# Schematic_Processo_Seletivo.net
KiCad netlist of a schematic drawn in Altium Designer
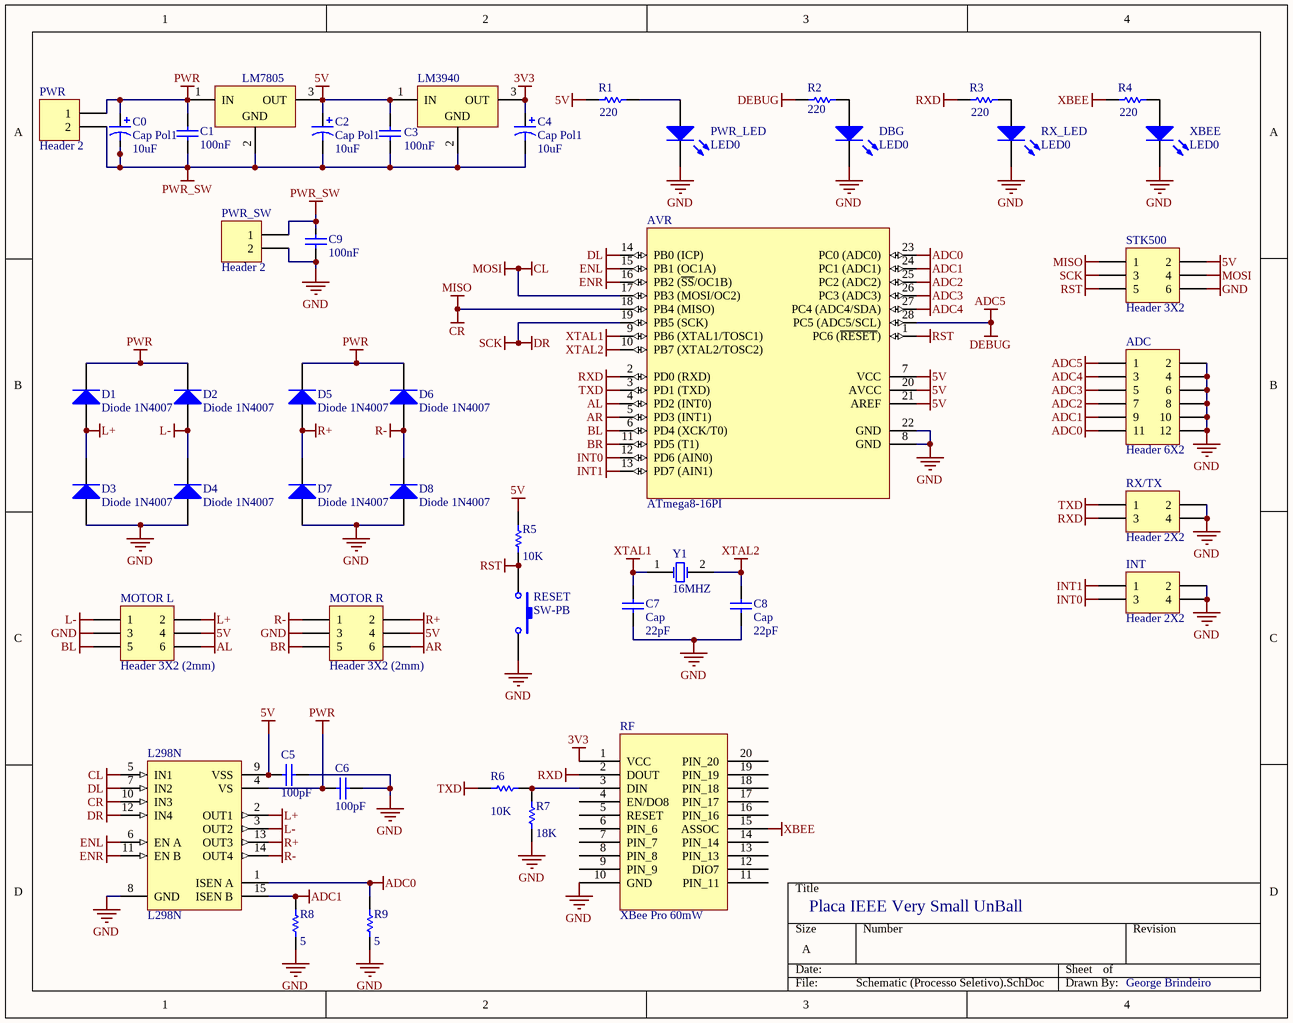
[diagram p0: Schematic (Processo Seletivo).SchDoc]

(export (version "E")
  (design (tool "Eeschema 10.0.6"))
  (components
    (comp (ref "ADC")
      (value "Header 6X2")
      (footprint "HDR2X6")
      (description "Header, 6-Pin, Dual row")
      (fields (field (name "PUBLISHER") "Altium Limited"))
      (libsource (lib "Miscellaneous Connectors") (part "Header 6X2"))
    )
    (comp (ref "AVR")
      (value "ATmega8-16PI")
      (footprint "28P3")
      (description "8-Bit AVR Microcontroller with 8K Bytes of In-System Programmable Flash Memory")
      (fields (field (name "PUBLISHER") "Altium Limited"))
      (libsource (lib "Atmel Microcontroller 8-Bit AVR") (part "ATmega8-16PI"))
    )
    (comp (ref "C0")
      (value "Cap Pol1")
      (footprint "B")
      (description "Polarized Capacitor (Radial)")
      (fields (field (name "ALTIUM_VALUE") "10uF") (field (name "PUBLISHER") "Altium Limited"))
      (libsource (lib "Miscellaneous Devices") (part "Cap Pol1"))
    )
    (comp (ref "C1")
      (value "100nF")
      (footprint "C_NANO_HOLES")
      (description "Capacitor")
      (fields (field (name "Comment") "Cap") (field (name "PUBLISHER") "Altium Limited"))
      (libsource (lib "Miscellaneous Devices") (part "Cap"))
    )
    (comp (ref "C2")
      (value "Cap Pol1")
      (footprint "B")
      (description "Polarized Capacitor (Radial)")
      (fields (field (name "ALTIUM_VALUE") "10uF") (field (name "PUBLISHER") "Altium Limited"))
      (libsource (lib "Miscellaneous Devices") (part "Cap Pol1"))
    )
    (comp (ref "C3")
      (value "100nF")
      (footprint "C_NANO_HOLES")
      (description "Capacitor")
      (fields (field (name "Comment") "Cap") (field (name "PUBLISHER") "Altium Limited"))
      (libsource (lib "Miscellaneous Devices") (part "Cap"))
    )
    (comp (ref "C4")
      (value "Cap Pol1")
      (footprint "B")
      (description "Polarized Capacitor (Radial)")
      (fields (field (name "ALTIUM_VALUE") "10uF") (field (name "PUBLISHER") "Altium Limited"))
      (libsource (lib "Miscellaneous Devices") (part "Cap Pol1"))
    )
    (comp (ref "C5")
      (value "100pF")
      (footprint "C_NANO_HOLES")
      (description "Capacitor")
      (fields (field (name "Comment") "Cap") (field (name "PUBLISHER") "Altium Limited"))
      (libsource (lib "Miscellaneous Devices") (part "Cap"))
    )
    (comp (ref "C6")
      (value "100pF")
      (footprint "C_NANO_HOLES")
      (description "Capacitor")
      (fields (field (name "Comment") "Cap") (field (name "PUBLISHER") "Altium Limited"))
      (libsource (lib "Miscellaneous Devices") (part "Cap"))
    )
    (comp (ref "C7")
      (value "Cap")
      (footprint "C_NANO_HOLES")
      (description "Capacitor")
      (fields (field (name "ALTIUM_VALUE") "22pF") (field (name "PUBLISHER") "Altium Limited"))
      (libsource (lib "Miscellaneous Devices") (part "Cap"))
    )
    (comp (ref "C8")
      (value "Cap")
      (footprint "C_NANO_HOLES")
      (description "Capacitor")
      (fields (field (name "ALTIUM_VALUE") "22pF") (field (name "PUBLISHER") "Altium Limited"))
      (libsource (lib "Miscellaneous Devices") (part "Cap"))
    )
    (comp (ref "C9")
      (value "100nF")
      (footprint "C_NANO_HOLES")
      (description "Capacitor")
      (fields (field (name "Comment") "Cap") (field (name "PUBLISHER") "Altium Limited"))
      (libsource (lib "Miscellaneous Devices") (part "Cap"))
    )
    (comp (ref "D1")
      (value "Diode 1N4007")
      (footprint "DO-41")
      (description "1 Amp General Purpose Rectifier")
      (fields (field (name "PUBLISHER") "Altium Limited"))
      (libsource (lib "Miscellaneous Devices") (part "Diode 1N4007"))
    )
    (comp (ref "D2")
      (value "Diode 1N4007")
      (footprint "DO-41")
      (description "1 Amp General Purpose Rectifier")
      (fields (field (name "PUBLISHER") "Altium Limited"))
      (libsource (lib "Miscellaneous Devices") (part "Diode 1N4007"))
    )
    (comp (ref "D3")
      (value "Diode 1N4007")
      (footprint "DO-41")
      (description "1 Amp General Purpose Rectifier")
      (fields (field (name "PUBLISHER") "Altium Limited"))
      (libsource (lib "Miscellaneous Devices") (part "Diode 1N4007"))
    )
    (comp (ref "D4")
      (value "Diode 1N4007")
      (footprint "DO-41")
      (description "1 Amp General Purpose Rectifier")
      (fields (field (name "PUBLISHER") "Altium Limited"))
      (libsource (lib "Miscellaneous Devices") (part "Diode 1N4007"))
    )
    (comp (ref "D5")
      (value "Diode 1N4007")
      (footprint "DO-41")
      (description "1 Amp General Purpose Rectifier")
      (fields (field (name "PUBLISHER") "Altium Limited"))
      (libsource (lib "Miscellaneous Devices") (part "Diode 1N4007"))
    )
    (comp (ref "D6")
      (value "Diode 1N4007")
      (footprint "DO-41")
      (description "1 Amp General Purpose Rectifier")
      (fields (field (name "PUBLISHER") "Altium Limited"))
      (libsource (lib "Miscellaneous Devices") (part "Diode 1N4007"))
    )
    (comp (ref "D7")
      (value "Diode 1N4007")
      (footprint "DO-41")
      (description "1 Amp General Purpose Rectifier")
      (fields (field (name "PUBLISHER") "Altium Limited"))
      (libsource (lib "Miscellaneous Devices") (part "Diode 1N4007"))
    )
    (comp (ref "D8")
      (value "Diode 1N4007")
      (footprint "DO-41")
      (description "1 Amp General Purpose Rectifier")
      (fields (field (name "PUBLISHER") "Altium Limited"))
      (libsource (lib "Miscellaneous Devices") (part "Diode 1N4007"))
    )
    (comp (ref "DBG")
      (value "LED0")
      (footprint "B")
      (description "Typical INFRARED GaAs LED")
      (fields (field (name "PUBLISHER") "Altium Limited"))
      (libsource (lib "Miscellaneous Devices") (part "LED0"))
    )
    (comp (ref "INT")
      (value "Header 2X2")
      (footprint "HDR2X2")
      (description "Header, 2-Pin, Dual row")
      (fields (field (name "PUBLISHER") "Altium Limited"))
      (libsource (lib "Miscellaneous Connectors") (part "Header 2X2"))
    )
    (comp (ref "L298N")
      (value "L298N")
      (footprint "Multiwatt15V")
      (description "Dual Full Bridge Driver")
      (fields (field (name "PUBLISHER") "Altium Limited"))
      (libsource (lib "ST Interface DC Motor Controller") (part "L298N"))
    )
    (comp (ref "LM3940")
      (value "LM3940IT-3.3")
      (footprint "T03B")
      (description "1A Low Dropout Regulator for 5V to 3.3V Conversion")
      (fields
        (field (name "MANUFACTURER") "National Semiconductor")
        (field (name "DIGIKEYPARTNUMBER") "LM3940IT-3.3-ND")
        (field (name "PUBLISHER") "Altium Limited")
      )
      (libsource (lib "NSC LDO") (part "LM3940IT-3.3"))
    )
    (comp (ref "LM7805")
      (value "µA7805CKC")
      (footprint "KC03")
      (description "Positive-Voltage Regulator")
      (fields (field (name "PUBLISHER") "Altium Limited"))
      (libsource (lib "TI Power Mgt Voltage Regulator") (part "µA7805CKC"))
    )
    (comp (ref "MOTOR L")
      (value "Header 3X2 (2mm)")
      (footprint "HDR2x3_2MM")
      (description "Header, 3-Pin, Dual row")
      (fields (field (name "PUBLISHER") "Altium Limited"))
      (libsource (lib "Miscellaneous Connectors") (part "Header 3X2"))
    )
    (comp (ref "MOTOR R")
      (value "Header 3X2 (2mm)")
      (footprint "HDR2x3_2MM")
      (description "Header, 3-Pin, Dual row")
      (fields (field (name "PUBLISHER") "Altium Limited"))
      (libsource (lib "Miscellaneous Connectors") (part "Header 3X2"))
    )
    (comp (ref "PWR")
      (value "Header 2")
      (footprint "HDR1X2")
      (description "Header, 2-Pin")
      (fields (field (name "PUBLISHER") "Altium Limited"))
      (libsource (lib "Miscellaneous Connectors") (part "Header 2"))
    )
    (comp (ref "PWR_LED")
      (value "LED0")
      (footprint "B")
      (description "Typical INFRARED GaAs LED")
      (fields (field (name "PUBLISHER") "Altium Limited"))
      (libsource (lib "Miscellaneous Devices") (part "LED0"))
    )
    (comp (ref "PWR_SW")
      (value "Header 2")
      (footprint "HDR1X2")
      (description "Header, 2-Pin")
      (fields (field (name "PUBLISHER") "Altium Limited"))
      (libsource (lib "Miscellaneous Connectors") (part "Header 2"))
    )
    (comp (ref "R1")
      (value "220")
      (footprint "AXIAL-0.3")
      (description "Resistor")
      (fields (field (name "PUBLISHER") "Altium Limited"))
      (libsource (lib "Miscellaneous Devices") (part "Res1"))
    )
    (comp (ref "R2")
      (value "220")
      (footprint "AXIAL-0.3")
      (description "Resistor")
      (fields (field (name "PUBLISHER") "Altium Limited"))
      (libsource (lib "Miscellaneous Devices") (part "Res1"))
    )
    (comp (ref "R3")
      (value "220")
      (footprint "AXIAL-0.3")
      (description "Resistor")
      (fields (field (name "PUBLISHER") "Altium Limited"))
      (libsource (lib "Miscellaneous Devices") (part "Res1"))
    )
    (comp (ref "R4")
      (value "220")
      (footprint "AXIAL-0.3")
      (description "Resistor")
      (fields (field (name "PUBLISHER") "Altium Limited"))
      (libsource (lib "Miscellaneous Devices") (part "Res1"))
    )
    (comp (ref "R5")
      (value "10K")
      (footprint "AXIAL-0.3")
      (description "Resistor")
      (fields (field (name "PUBLISHER") "Altium Limited"))
      (libsource (lib "Miscellaneous Devices") (part "Res1"))
    )
    (comp (ref "R6")
      (value "10K")
      (footprint "AXIAL-0.3")
      (description "Resistor")
      (fields (field (name "PUBLISHER") "Altium Limited"))
      (libsource (lib "Miscellaneous Devices") (part "Res1"))
    )
    (comp (ref "R7")
      (value "18K")
      (footprint "AXIAL-0.3")
      (description "Resistor")
      (fields (field (name "PUBLISHER") "Altium Limited"))
      (libsource (lib "Miscellaneous Devices") (part "Res1"))
    )
    (comp (ref "R8")
      (value "5")
      (footprint "AXIAL-0.3")
      (description "Resistor")
      (fields (field (name "PUBLISHER") "Altium Limited"))
      (libsource (lib "Miscellaneous Devices") (part "Res1"))
    )
    (comp (ref "R9")
      (value "5")
      (footprint "AXIAL-0.3")
      (description "Resistor")
      (fields (field (name "PUBLISHER") "Altium Limited"))
      (libsource (lib "Miscellaneous Devices") (part "Res1"))
    )
    (comp (ref "RESET")
      (value "SW-PB")
      (footprint "PUSHBUTTON")
      (description "Switch")
      (fields (field (name "PUBLISHER") "Altium Limited"))
      (libsource (lib "Miscellaneous Devices") (part "SW-PB"))
    )
    (comp (ref "RF") (value "XBee Pro 60mW") (footprint "XBEE_PRO") (libsource (lib "Schlib") (part "XBee")))
    (comp (ref "RX/TX")
      (value "Header 2X2")
      (footprint "HDR2X2")
      (description "Header, 2-Pin, Dual row")
      (fields (field (name "PUBLISHER") "Altium Limited"))
      (libsource (lib "Miscellaneous Connectors") (part "Header 2X2"))
    )
    (comp (ref "RX_LED")
      (value "LED0")
      (footprint "B")
      (description "Typical INFRARED GaAs LED")
      (fields (field (name "PUBLISHER") "Altium Limited"))
      (libsource (lib "Miscellaneous Devices") (part "LED0"))
    )
    (comp (ref "STK500")
      (value "Header 3X2")
      (footprint "HDR2X3")
      (description "Header, 3-Pin, Dual row")
      (fields (field (name "PUBLISHER") "Altium Limited"))
      (libsource (lib "Miscellaneous Connectors") (part "Header 3X2"))
    )
    (comp (ref "XBEE")
      (value "LED0")
      (footprint "B")
      (description "Typical INFRARED GaAs LED")
      (fields (field (name "PUBLISHER") "Altium Limited"))
      (libsource (lib "Miscellaneous Devices") (part "LED0"))
    )
    (comp (ref "Y1")
      (value "16MHZ")
      (footprint "BCY-W2/E4.7")
      (description "Crystal Oscillator")
      (fields (field (name "PUBLISHER") "Altium Limited"))
      (libsource (lib "ECS Crystal Oscillator") (part "ECS-120-32-1"))
    )
  )
  (nets
    (net (code "1") (name "3V3") (class "Default")
      (node (ref "C4") (pin "1") (pinfunction "1_1") (pintype "passive"))
      (node (ref "LM3940") (pin "3") (pinfunction "OUT_3") (pintype "power_in"))
      (node (ref "RF") (pin "1") (pinfunction "VCC_1") (pintype "passive"))
    )
    (net (code "2") (name "5V") (class "Default")
      (node (ref "AVR") (pin "20") (pinfunction "AVCC_20") (pintype "power_in"))
      (node (ref "AVR") (pin "21") (pinfunction "AREF_21") (pintype "passive"))
      (node (ref "AVR") (pin "7") (pinfunction "VCC_7") (pintype "power_in"))
      (node (ref "C2") (pin "1") (pinfunction "1_1") (pintype "passive"))
      (node (ref "C3") (pin "1") (pinfunction "1_1") (pintype "passive"))
      (node (ref "C5") (pin "1") (pinfunction "1_1") (pintype "passive"))
      (node (ref "L298N") (pin "9") (pinfunction "VSS_9") (pintype "power_in"))
      (node (ref "LM3940") (pin "1") (pinfunction "IN_1") (pintype "power_in"))
      (node (ref "LM7805") (pin "3") (pinfunction "OUT_3") (pintype "power_in"))
      (node (ref "MOTOR L") (pin "4") (pinfunction "4_4") (pintype "passive"))
      (node (ref "MOTOR R") (pin "4") (pinfunction "4_4") (pintype "passive"))
      (node (ref "R1") (pin "1") (pinfunction "1_1") (pintype "passive"))
      (node (ref "R5") (pin "2") (pinfunction "2_2") (pintype "passive"))
      (node (ref "STK500") (pin "2") (pinfunction "2_2") (pintype "passive"))
    )
    (net (code "3") (name "ADC0") (class "Default")
      (node (ref "ADC") (pin "11") (pinfunction "11_11") (pintype "passive"))
      (node (ref "AVR") (pin "23") (pinfunction "PC0_(ADC0)_23") (pintype "bidirectional"))
      (node (ref "L298N") (pin "1") (pinfunction "ISEN_A_1") (pintype "passive"))
      (node (ref "R9") (pin "2") (pinfunction "2_2") (pintype "passive"))
    )
    (net (code "4") (name "ADC1") (class "Default")
      (node (ref "ADC") (pin "9") (pinfunction "9_9") (pintype "passive"))
      (node (ref "AVR") (pin "24") (pinfunction "PC1_(ADC1)_24") (pintype "bidirectional"))
      (node (ref "L298N") (pin "15") (pinfunction "ISEN_B_15") (pintype "passive"))
      (node (ref "R8") (pin "2") (pinfunction "2_2") (pintype "passive"))
    )
    (net (code "5") (name "ADC2") (class "Default")
      (node (ref "ADC") (pin "7") (pinfunction "7_7") (pintype "passive"))
      (node (ref "AVR") (pin "25") (pinfunction "PC2_(ADC2)_25") (pintype "bidirectional"))
    )
    (net (code "6") (name "ADC3") (class "Default")
      (node (ref "ADC") (pin "5") (pinfunction "5_5") (pintype "passive"))
      (node (ref "AVR") (pin "26") (pinfunction "PC3_(ADC3)_26") (pintype "bidirectional"))
    )
    (net (code "7") (name "ADC4") (class "Default")
      (node (ref "ADC") (pin "3") (pinfunction "3_3") (pintype "passive"))
      (node (ref "AVR") (pin "27") (pinfunction "PC4_(ADC4/SDA)_27") (pintype "bidirectional"))
    )
    (net (code "8") (name "ADC5") (class "Default")
      (node (ref "ADC") (pin "1") (pinfunction "1_1") (pintype "passive"))
      (node (ref "AVR") (pin "28") (pinfunction "PC5_(ADC5/SCL)_28") (pintype "bidirectional"))
      (node (ref "R2") (pin "1") (pinfunction "1_1") (pintype "passive"))
    )
    (net (code "9") (name "AL") (class "Default")
      (node (ref "AVR") (pin "4") (pinfunction "PD2_(INT0)_4") (pintype "bidirectional"))
      (node (ref "MOTOR L") (pin "6") (pinfunction "6_6") (pintype "passive"))
    )
    (net (code "10") (name "AR") (class "Default")
      (node (ref "AVR") (pin "5") (pinfunction "PD3_(INT1)_5") (pintype "bidirectional"))
      (node (ref "MOTOR R") (pin "6") (pinfunction "6_6") (pintype "passive"))
    )
    (net (code "11") (name "BL") (class "Default")
      (node (ref "AVR") (pin "6") (pinfunction "PD4_(XCK/T0)_6") (pintype "bidirectional"))
      (node (ref "MOTOR L") (pin "5") (pinfunction "5_5") (pintype "passive"))
    )
    (net (code "12") (name "BR") (class "Default")
      (node (ref "AVR") (pin "11") (pinfunction "PD5_(T1)_11") (pintype "bidirectional"))
      (node (ref "MOTOR R") (pin "5") (pinfunction "5_5") (pintype "passive"))
    )
    (net (code "13") (name "CL") (class "Default")
      (node (ref "AVR") (pin "17") (pinfunction "PB3_(MOSI/OC2)_17") (pintype "bidirectional"))
      (node (ref "L298N") (pin "5") (pinfunction "IN1_5") (pintype "input"))
      (node (ref "STK500") (pin "4") (pinfunction "4_4") (pintype "passive"))
    )
    (net (code "14") (name "CR") (class "Default")
      (node (ref "AVR") (pin "18") (pinfunction "PB4_(MISO)_18") (pintype "bidirectional"))
      (node (ref "L298N") (pin "10") (pinfunction "IN3_10") (pintype "input"))
      (node (ref "STK500") (pin "1") (pinfunction "1_1") (pintype "passive"))
    )
    (net (code "15") (name "DL") (class "Default")
      (node (ref "AVR") (pin "14") (pinfunction "PB0_(ICP)_14") (pintype "bidirectional"))
      (node (ref "L298N") (pin "7") (pinfunction "IN2_7") (pintype "input"))
    )
    (net (code "16") (name "DR") (class "Default")
      (node (ref "AVR") (pin "19") (pinfunction "PB5_(SCK)_19") (pintype "bidirectional"))
      (node (ref "L298N") (pin "12") (pinfunction "IN4_12") (pintype "input"))
      (node (ref "STK500") (pin "3") (pinfunction "3_3") (pintype "passive"))
    )
    (net (code "17") (name "ENL") (class "Default")
      (node (ref "AVR") (pin "15") (pinfunction "PB1_(OC1A)_15") (pintype "bidirectional"))
      (node (ref "L298N") (pin "6") (pinfunction "EN_A_6") (pintype "input"))
    )
    (net (code "18") (name "ENR") (class "Default")
      (node (ref "AVR") (pin "16") (pinfunction "PB2_(~{SS}/OC1B)_16") (pintype "bidirectional"))
      (node (ref "L298N") (pin "11") (pinfunction "EN_B_11") (pintype "input"))
    )
    (net (code "19") (name "GND") (class "Default")
      (node (ref "ADC") (pin "10") (pinfunction "10_10") (pintype "passive"))
      (node (ref "ADC") (pin "12") (pinfunction "12_12") (pintype "passive"))
      (node (ref "ADC") (pin "2") (pinfunction "2_2") (pintype "passive"))
      (node (ref "ADC") (pin "4") (pinfunction "4_4") (pintype "passive"))
      (node (ref "ADC") (pin "6") (pinfunction "6_6") (pintype "passive"))
      (node (ref "ADC") (pin "8") (pinfunction "8_8") (pintype "passive"))
      (node (ref "AVR") (pin "22") (pinfunction "GND_22") (pintype "power_in"))
      (node (ref "AVR") (pin "8") (pinfunction "GND_8") (pintype "power_in"))
      (node (ref "C5") (pin "2") (pinfunction "2_2") (pintype "passive"))
      (node (ref "C6") (pin "2") (pinfunction "2_2") (pintype "passive"))
      (node (ref "C7") (pin "2") (pinfunction "2_2") (pintype "passive"))
      (node (ref "C8") (pin "2") (pinfunction "2_2") (pintype "passive"))
      (node (ref "C9") (pin "2") (pinfunction "2_2") (pintype "passive"))
      (node (ref "D3") (pin "1") (pinfunction "A_1") (pintype "passive"))
      (node (ref "D4") (pin "1") (pinfunction "A_1") (pintype "passive"))
      (node (ref "D7") (pin "1") (pinfunction "A_1") (pintype "passive"))
      (node (ref "D8") (pin "1") (pinfunction "A_1") (pintype "passive"))
      (node (ref "DBG") (pin "2") (pinfunction "K_2") (pintype "passive"))
      (node (ref "INT") (pin "2") (pinfunction "2_2") (pintype "passive"))
      (node (ref "INT") (pin "4") (pinfunction "4_4") (pintype "passive"))
      (node (ref "L298N") (pin "8") (pinfunction "GND_8") (pintype "power_in"))
      (node (ref "MOTOR L") (pin "3") (pinfunction "3_3") (pintype "passive"))
      (node (ref "MOTOR R") (pin "3") (pinfunction "3_3") (pintype "passive"))
      (node (ref "PWR_LED") (pin "2") (pinfunction "K_2") (pintype "passive"))
      (node (ref "PWR_SW") (pin "2") (pinfunction "2_2") (pintype "passive"))
      (node (ref "R7") (pin "2") (pinfunction "2_2") (pintype "passive"))
      (node (ref "R8") (pin "1") (pinfunction "1_1") (pintype "passive"))
      (node (ref "R9") (pin "1") (pinfunction "1_1") (pintype "passive"))
      (node (ref "RESET") (pin "2") (pinfunction "2_2") (pintype "passive"))
      (node (ref "RF") (pin "10") (pinfunction "GND_10") (pintype "passive"))
      (node (ref "RX/TX") (pin "2") (pinfunction "2_2") (pintype "passive"))
      (node (ref "RX/TX") (pin "4") (pinfunction "4_4") (pintype "passive"))
      (node (ref "RX_LED") (pin "2") (pinfunction "K_2") (pintype "passive"))
      (node (ref "STK500") (pin "6") (pinfunction "6_6") (pintype "passive"))
      (node (ref "XBEE") (pin "2") (pinfunction "K_2") (pintype "passive"))
    )
    (net (code "20") (name "INT0") (class "Default")
      (node (ref "AVR") (pin "12") (pinfunction "PD6_(AIN0)_12") (pintype "bidirectional"))
      (node (ref "INT") (pin "3") (pinfunction "3_3") (pintype "passive"))
    )
    (net (code "21") (name "INT1") (class "Default")
      (node (ref "AVR") (pin "13") (pinfunction "PD7_(AIN1)_13") (pintype "bidirectional"))
      (node (ref "INT") (pin "1") (pinfunction "1_1") (pintype "passive"))
    )
    (net (code "22") (name "L+") (class "Default")
      (node (ref "D1") (pin "1") (pinfunction "A_1") (pintype "passive"))
      (node (ref "D3") (pin "2") (pinfunction "K_2") (pintype "passive"))
      (node (ref "L298N") (pin "2") (pinfunction "OUT1_2") (pintype "output"))
      (node (ref "MOTOR L") (pin "2") (pinfunction "2_2") (pintype "passive"))
    )
    (net (code "23") (name "L-") (class "Default")
      (node (ref "D2") (pin "1") (pinfunction "A_1") (pintype "passive"))
      (node (ref "D4") (pin "2") (pinfunction "K_2") (pintype "passive"))
      (node (ref "L298N") (pin "3") (pinfunction "OUT2_3") (pintype "output"))
      (node (ref "MOTOR L") (pin "1") (pinfunction "1_1") (pintype "passive"))
    )
    (net (code "24") (name "Net-(DBG-A)") (class "Default")
      (node (ref "DBG") (pin "1") (pinfunction "A_1") (pintype "passive"))
      (node (ref "R2") (pin "2") (pinfunction "2_2") (pintype "passive"))
    )
    (net (code "25") (name "Net-(PWR_LED-A)") (class "Default")
      (node (ref "PWR_LED") (pin "1") (pinfunction "A_1") (pintype "passive"))
      (node (ref "R1") (pin "2") (pinfunction "2_2") (pintype "passive"))
    )
    (net (code "26") (name "Net-(RF-DIN)") (class "Default")
      (node (ref "R6") (pin "1") (pinfunction "1_1") (pintype "passive"))
      (node (ref "R7") (pin "1") (pinfunction "1_1") (pintype "passive"))
      (node (ref "RF") (pin "3") (pinfunction "DIN_3") (pintype "passive"))
    )
    (net (code "27") (name "Net-(RX_LED-A)") (class "Default")
      (node (ref "R3") (pin "2") (pinfunction "2_2") (pintype "passive"))
      (node (ref "RX_LED") (pin "1") (pinfunction "A_1") (pintype "passive"))
    )
    (net (code "28") (name "Net-(XBEE-A)") (class "Default")
      (node (ref "R4") (pin "2") (pinfunction "2_2") (pintype "passive"))
      (node (ref "XBEE") (pin "1") (pinfunction "A_1") (pintype "passive"))
    )
    (net (code "29") (name "PWR") (class "Default")
      (node (ref "C0") (pin "1") (pinfunction "1_1") (pintype "passive"))
      (node (ref "C1") (pin "1") (pinfunction "1_1") (pintype "passive"))
      (node (ref "C6") (pin "1") (pinfunction "1_1") (pintype "passive"))
      (node (ref "D1") (pin "2") (pinfunction "K_2") (pintype "passive"))
      (node (ref "D2") (pin "2") (pinfunction "K_2") (pintype "passive"))
      (node (ref "D5") (pin "2") (pinfunction "K_2") (pintype "passive"))
      (node (ref "D6") (pin "2") (pinfunction "K_2") (pintype "passive"))
      (node (ref "L298N") (pin "4") (pinfunction "VS_4") (pintype "power_in"))
      (node (ref "LM7805") (pin "1") (pinfunction "IN_1") (pintype "power_in"))
      (node (ref "PWR") (pin "1") (pinfunction "1_1") (pintype "passive"))
    )
    (net (code "30") (name "PWR_SW") (class "Default")
      (node (ref "C0") (pin "2") (pinfunction "2_2") (pintype "passive"))
      (node (ref "C1") (pin "2") (pinfunction "2_2") (pintype "passive"))
      (node (ref "C2") (pin "2") (pinfunction "2_2") (pintype "passive"))
      (node (ref "C3") (pin "2") (pinfunction "2_2") (pintype "passive"))
      (node (ref "C4") (pin "2") (pinfunction "2_2") (pintype "passive"))
      (node (ref "C9") (pin "1") (pinfunction "1_1") (pintype "passive"))
      (node (ref "LM3940") (pin "2") (pinfunction "GND_2") (pintype "power_in"))
      (node (ref "LM7805") (pin "2") (pinfunction "GND_2") (pintype "power_in"))
      (node (ref "PWR") (pin "2") (pinfunction "2_2") (pintype "passive"))
      (node (ref "PWR_SW") (pin "1") (pinfunction "1_1") (pintype "passive"))
    )
    (net (code "31") (name "R+") (class "Default")
      (node (ref "D5") (pin "1") (pinfunction "A_1") (pintype "passive"))
      (node (ref "D7") (pin "2") (pinfunction "K_2") (pintype "passive"))
      (node (ref "L298N") (pin "13") (pinfunction "OUT3_13") (pintype "output"))
      (node (ref "MOTOR R") (pin "2") (pinfunction "2_2") (pintype "passive"))
    )
    (net (code "32") (name "R-") (class "Default")
      (node (ref "D6") (pin "1") (pinfunction "A_1") (pintype "passive"))
      (node (ref "D8") (pin "2") (pinfunction "K_2") (pintype "passive"))
      (node (ref "L298N") (pin "14") (pinfunction "OUT4_14") (pintype "output"))
      (node (ref "MOTOR R") (pin "1") (pinfunction "1_1") (pintype "passive"))
    )
    (net (code "33") (name "RST") (class "Default")
      (node (ref "AVR") (pin "1") (pinfunction "PC6_(~{RESET})_1") (pintype "bidirectional"))
      (node (ref "R5") (pin "1") (pinfunction "1_1") (pintype "passive"))
      (node (ref "RESET") (pin "1") (pinfunction "1_1") (pintype "passive"))
      (node (ref "STK500") (pin "5") (pinfunction "5_5") (pintype "passive"))
    )
    (net (code "34") (name "RXD") (class "Default")
      (node (ref "AVR") (pin "2") (pinfunction "PD0_(RXD)_2") (pintype "bidirectional"))
      (node (ref "R3") (pin "1") (pinfunction "1_1") (pintype "passive"))
      (node (ref "RF") (pin "2") (pinfunction "DOUT_2") (pintype "passive"))
      (node (ref "RX/TX") (pin "3") (pinfunction "3_3") (pintype "passive"))
    )
    (net (code "35") (name "TXD") (class "Default")
      (node (ref "AVR") (pin "3") (pinfunction "PD1_(TXD)_3") (pintype "bidirectional"))
      (node (ref "R6") (pin "2") (pinfunction "2_2") (pintype "passive"))
      (node (ref "RX/TX") (pin "1") (pinfunction "1_1") (pintype "passive"))
    )
    (net (code "36") (name "XBEE") (class "Default")
      (node (ref "R4") (pin "1") (pinfunction "1_1") (pintype "passive"))
      (node (ref "RF") (pin "15") (pinfunction "ASSOC_15") (pintype "passive"))
    )
    (net (code "37") (name "XTAL1") (class "Default")
      (node (ref "AVR") (pin "9") (pinfunction "PB6_(XTAL1/TOSC1)_9") (pintype "bidirectional"))
      (node (ref "C7") (pin "1") (pinfunction "1_1") (pintype "passive"))
      (node (ref "Y1") (pin "1") (pinfunction "OSC1_1") (pintype "passive"))
    )
    (net (code "38") (name "XTAL2") (class "Default")
      (node (ref "AVR") (pin "10") (pinfunction "PB7_(XTAL2/TOSC2)_10") (pintype "bidirectional"))
      (node (ref "C8") (pin "1") (pinfunction "1_1") (pintype "passive"))
      (node (ref "Y1") (pin "2") (pinfunction "OSC2_2") (pintype "passive"))
    )
    (net (code "39") (name "unconnected-(RF-DIO7-Pad12)") (class "Default")
      (node (ref "RF") (pin "12") (pinfunction "DIO7_12") (pintype "passive"))
    )
    (net (code "40") (name "unconnected-(RF-EN{slash}DO8-Pad4)") (class "Default")
      (node (ref "RF") (pin "4") (pinfunction "EN/DO8_4") (pintype "passive"))
    )
    (net (code "41") (name "unconnected-(RF-PIN_6-Pad6)") (class "Default")
      (node (ref "RF") (pin "6") (pinfunction "PIN_6_6") (pintype "passive"))
    )
    (net (code "42") (name "unconnected-(RF-PIN_7-Pad7)") (class "Default")
      (node (ref "RF") (pin "7") (pinfunction "PIN_7_7") (pintype "passive"))
    )
    (net (code "43") (name "unconnected-(RF-PIN_8-Pad8)") (class "Default")
      (node (ref "RF") (pin "8") (pinfunction "PIN_8_8") (pintype "passive"))
    )
    (net (code "44") (name "unconnected-(RF-PIN_9-Pad9)") (class "Default")
      (node (ref "RF") (pin "9") (pinfunction "PIN_9_9") (pintype "passive"))
    )
    (net (code "45") (name "unconnected-(RF-PIN_11-Pad11)") (class "Default")
      (node (ref "RF") (pin "11") (pinfunction "PIN_11_11") (pintype "passive"))
    )
    (net (code "46") (name "unconnected-(RF-PIN_13-Pad13)") (class "Default")
      (node (ref "RF") (pin "13") (pinfunction "PIN_13_13") (pintype "passive"))
    )
    (net (code "47") (name "unconnected-(RF-PIN_14-Pad14)") (class "Default")
      (node (ref "RF") (pin "14") (pinfunction "PIN_14_14") (pintype "passive"))
    )
    (net (code "48") (name "unconnected-(RF-PIN_16-Pad16)") (class "Default")
      (node (ref "RF") (pin "16") (pinfunction "PIN_16_16") (pintype "passive"))
    )
    (net (code "49") (name "unconnected-(RF-PIN_17-Pad17)") (class "Default")
      (node (ref "RF") (pin "17") (pinfunction "PIN_17_17") (pintype "passive"))
    )
    (net (code "50") (name "unconnected-(RF-PIN_18-Pad18)") (class "Default")
      (node (ref "RF") (pin "18") (pinfunction "PIN_18_18") (pintype "passive"))
    )
    (net (code "51") (name "unconnected-(RF-PIN_19-Pad19)") (class "Default")
      (node (ref "RF") (pin "19") (pinfunction "PIN_19_19") (pintype "passive"))
    )
    (net (code "52") (name "unconnected-(RF-PIN_20-Pad20)") (class "Default")
      (node (ref "RF") (pin "20") (pinfunction "PIN_20_20") (pintype "passive"))
    )
    (net (code "53") (name "unconnected-(RF-RESET-Pad5)") (class "Default")
      (node (ref "RF") (pin "5") (pinfunction "RESET_5") (pintype "passive"))
    )
  )
)
